# RGB_LED.net
KiCad netlist of a schematic drawn in Altium Designer
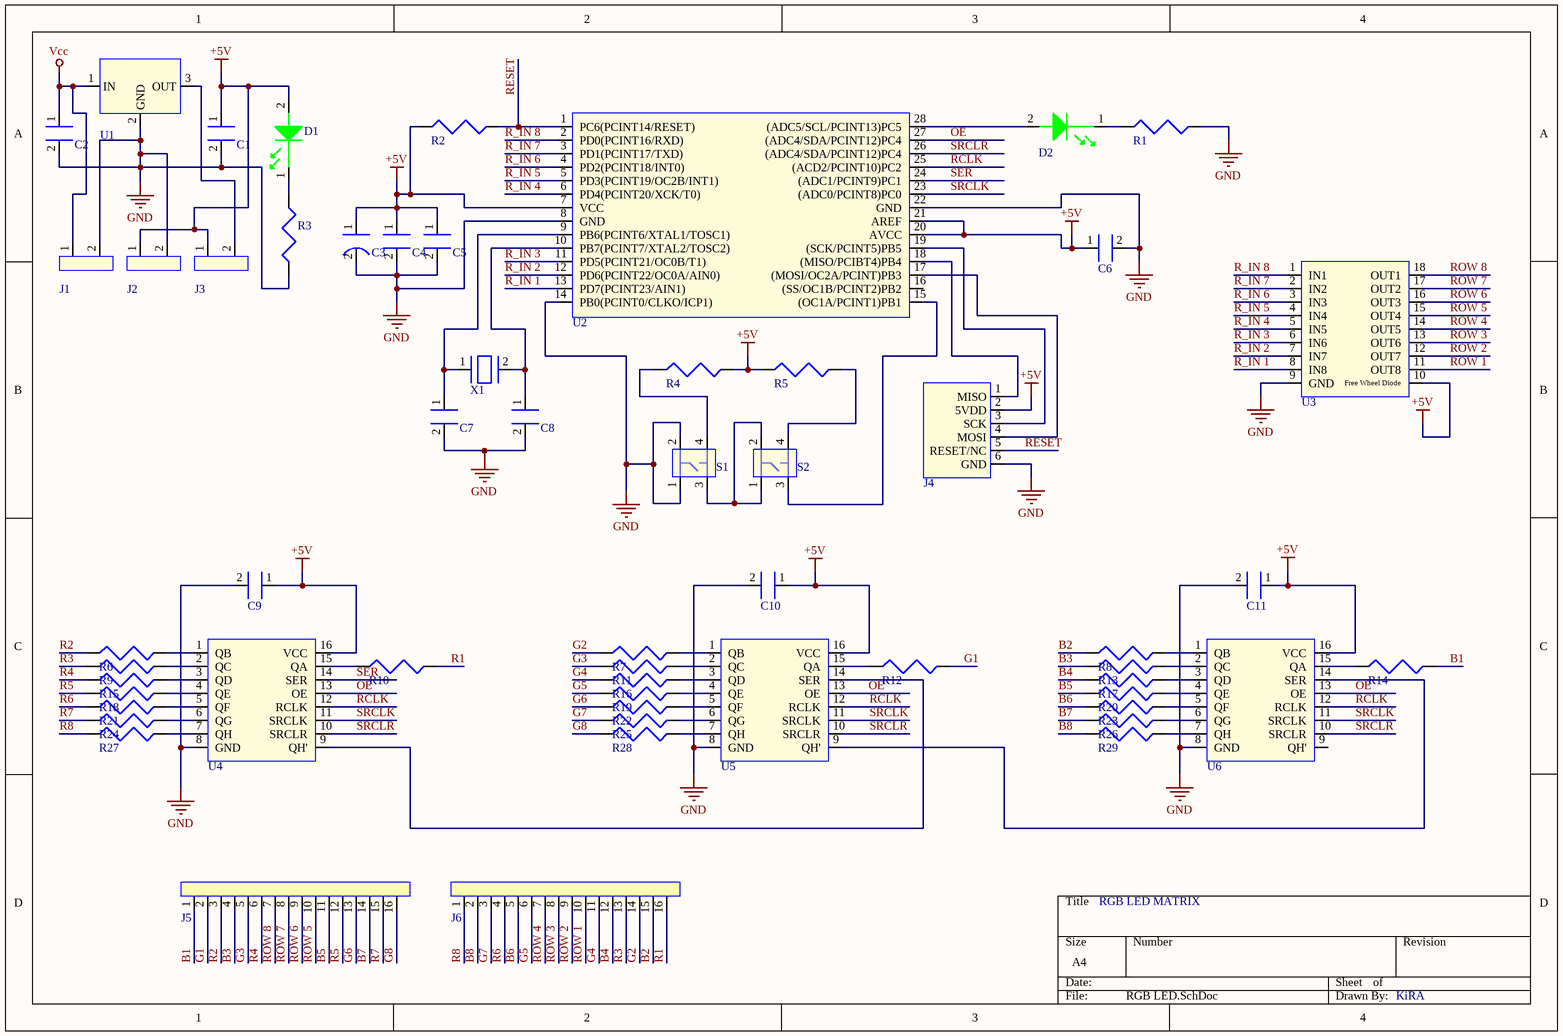
[diagram p0: RGB LED.SchDoc]

(export (version "E")
  (design (tool "Eeschema 10.0.6"))
  (components
    (comp (ref "C1")
      (value "10uF")
      (footprint "Cap 10uF 0805")
      (libsource (lib "RGB LED") (part "10uF 0805"))
    )
    (comp (ref "C2")
      (value "10uF")
      (footprint "Cap 10uF 0805")
      (libsource (lib "RGB LED") (part "10uF 0805"))
    )
    (comp (ref "C3")
      (value "47uF")
      (footprint "cap 47uF radial can")
      (fields
        (field (name "MANUFACTURER") "Panasonic Electronic Components")
        (field (name "TOLERANCE") "±20%")
      )
      (libsource (lib "RGB LED") (part "47uF Radial, Can -SMD"))
    )
    (comp (ref "C4")
      (value "10uF")
      (footprint "Cap 10uF 0805")
      (libsource (lib "RGB LED") (part "10uF 0805"))
    )
    (comp (ref "C5")
      (value "0.1uF")
      (footprint "Cap 0.1uF 0805")
      (libsource (lib "RGB LED") (part "0.1uF 0805"))
    )
    (comp (ref "C6")
      (value "0.1uF")
      (footprint "Cap 0.1uF 0805")
      (libsource (lib "RGB LED") (part "0.1uF 0805"))
    )
    (comp (ref "C7")
      (value "22pF")
      (footprint "CAP 22pF 0805")
      (libsource (lib "RGB LED") (part "22pF 0805"))
    )
    (comp (ref "C8")
      (value "22pF")
      (footprint "CAP 22pF 0805")
      (libsource (lib "RGB LED") (part "22pF 0805"))
    )
    (comp (ref "C9")
      (value "0.1uF")
      (footprint "Cap 0.1uF 0805")
      (libsource (lib "RGB LED") (part "0.1uF 0805"))
    )
    (comp (ref "C10")
      (value "0.1uF")
      (footprint "Cap 0.1uF 0805")
      (libsource (lib "RGB LED") (part "0.1uF 0805"))
    )
    (comp (ref "C11")
      (value "0.1uF")
      (footprint "Cap 0.1uF 0805")
      (libsource (lib "RGB LED") (part "0.1uF 0805"))
    )
    (comp (ref "D1")
      (value "LED 0805 Green")
      (footprint "LED 0805 Green")
      (fields (field (name "MANUFACTURER") "Lite-On Inc") (field (name "PART NO") "LTST-C171GKT"))
      (libsource (lib "RGB LED") (part "LED 0805 Green"))
    )
    (comp (ref "D2")
      (value "LED 0805 Green")
      (footprint "LED 0805 Green")
      (fields (field (name "MANUFACTURER") "Lite-On Inc") (field (name "PART NO") "LTST-C171GKT"))
      (libsource (lib "RGB LED") (part "LED 0805 Green"))
    )
    (comp (ref "J1")
      (value "Generic Header, 1X2 Vertical")
      (footprint "22232021")
      (fields (field (name "MANUFACTURER") "Molex") (field (name "PART NO") "22232021"))
      (libsource (lib "RGB LED") (part "2 pin male header"))
    )
    (comp (ref "J2")
      (value "Generic Header, 1X2 Vertical")
      (footprint "22232021")
      (fields (field (name "MANUFACTURER") "Molex") (field (name "PART NO") "22232021"))
      (libsource (lib "RGB LED") (part "2 pin male header"))
    )
    (comp (ref "J3")
      (value "Generic Header, 1X2 Vertical")
      (footprint "22232021")
      (fields (field (name "MANUFACTURER") "Molex") (field (name "PART NO") "22232021"))
      (libsource (lib "RGB LED") (part "2 pin male header"))
    )
    (comp (ref "J4")
      (value "6-Pin ISP header")
      (footprint "2X3 ISP header")
      (libsource (lib "RGB LED") (part "6-Pin ISP header"))
    )
    (comp (ref "J5")
      (value "16pin felmale header")
      (footprint "16 pins female header")
      (fields (field (name "MANUFACTURER") "4ucon technology inc"))
      (libsource (lib "RGB LED") (part "16pin felmale header"))
    )
    (comp (ref "J6")
      (value "16pin felmale header")
      (footprint "16 pins female header")
      (fields (field (name "MANUFACTURER") "4ucon technology inc"))
      (libsource (lib "RGB LED") (part "16pin felmale header"))
    )
    (comp (ref "R1")
      (value "200R")
      (footprint "RES 200R 0805")
      (fields
        (field (name "MANUFACTURER") "KOA Speer Electronics Inc")
        (field (name "PART NO") "RK73B2A")
        (field (name "POWER") "1/4W")
      )
      (libsource (lib "RGB LED") (part "Resistor 0805 200R"))
    )
    (comp (ref "R2")
      (value "10K")
      (footprint "RES 10K 0805")
      (fields
        (field (name "MANUFACTURER") "KOA Speer Electronics Inc")
        (field (name "PART NO") "RK73B2A")
        (field (name "POWER") "1/4W")
      )
      (libsource (lib "RGB LED") (part "Resistor 0805 10K"))
    )
    (comp (ref "R3")
      (value "200R")
      (footprint "RES 200R 0805")
      (fields
        (field (name "MANUFACTURER") "KOA Speer Electronics Inc")
        (field (name "PART NO") "RK73B2A")
        (field (name "POWER") "1/4W")
      )
      (libsource (lib "RGB LED") (part "Resistor 0805 200R"))
    )
    (comp (ref "R4")
      (value "10K")
      (footprint "RES 10K 0805")
      (fields
        (field (name "MANUFACTURER") "KOA Speer Electronics Inc")
        (field (name "PART NO") "RK73B2A")
        (field (name "POWER") "1/4W")
      )
      (libsource (lib "RGB LED") (part "Resistor 0805 10K"))
    )
    (comp (ref "R5")
      (value "10K")
      (footprint "RES 10K 0805")
      (fields
        (field (name "MANUFACTURER") "KOA Speer Electronics Inc")
        (field (name "PART NO") "RK73B2A")
        (field (name "POWER") "1/4W")
      )
      (libsource (lib "RGB LED") (part "Resistor 0805 10K"))
    )
    (comp (ref "R6")
      (value "Resistor 0805 100R")
      (footprint "RES 100R 0805")
      (fields
        (field (name "MANUFACTURER") "KOA Speer Electronics Inc")
        (field (name "PART NO") "RK73B2A")
        (field (name "POWER") "1/4W")
      )
      (libsource (lib "RGB LED") (part "Resistor 0805 100R"))
    )
    (comp (ref "R7")
      (value "Resistor 0805 100R")
      (footprint "RES 100R 0805")
      (fields
        (field (name "MANUFACTURER") "KOA Speer Electronics Inc")
        (field (name "PART NO") "RK73B2A")
        (field (name "POWER") "1/4W")
      )
      (libsource (lib "RGB LED") (part "Resistor 0805 100R"))
    )
    (comp (ref "R8")
      (value "Resistor 0805 100R")
      (footprint "RES 100R 0805")
      (fields
        (field (name "MANUFACTURER") "KOA Speer Electronics Inc")
        (field (name "PART NO") "RK73B2A")
        (field (name "POWER") "1/4W")
      )
      (libsource (lib "RGB LED") (part "Resistor 0805 100R"))
    )
    (comp (ref "R9")
      (value "Resistor 0805 100R")
      (footprint "RES 100R 0805")
      (fields
        (field (name "MANUFACTURER") "KOA Speer Electronics Inc")
        (field (name "PART NO") "RK73B2A")
        (field (name "POWER") "1/4W")
      )
      (libsource (lib "RGB LED") (part "Resistor 0805 100R"))
    )
    (comp (ref "R10")
      (value "Resistor 0805 100R")
      (footprint "RES 100R 0805")
      (fields
        (field (name "MANUFACTURER") "KOA Speer Electronics Inc")
        (field (name "PART NO") "RK73B2A")
        (field (name "POWER") "1/4W")
      )
      (libsource (lib "RGB LED") (part "Resistor 0805 100R"))
    )
    (comp (ref "R11")
      (value "Resistor 0805 100R")
      (footprint "RES 100R 0805")
      (fields
        (field (name "MANUFACTURER") "KOA Speer Electronics Inc")
        (field (name "PART NO") "RK73B2A")
        (field (name "POWER") "1/4W")
      )
      (libsource (lib "RGB LED") (part "Resistor 0805 100R"))
    )
    (comp (ref "R12")
      (value "Resistor 0805 100R")
      (footprint "RES 100R 0805")
      (fields
        (field (name "MANUFACTURER") "KOA Speer Electronics Inc")
        (field (name "PART NO") "RK73B2A")
        (field (name "POWER") "1/4W")
      )
      (libsource (lib "RGB LED") (part "Resistor 0805 100R"))
    )
    (comp (ref "R13")
      (value "Resistor 0805 100R")
      (footprint "RES 100R 0805")
      (fields
        (field (name "MANUFACTURER") "KOA Speer Electronics Inc")
        (field (name "PART NO") "RK73B2A")
        (field (name "POWER") "1/4W")
      )
      (libsource (lib "RGB LED") (part "Resistor 0805 100R"))
    )
    (comp (ref "R14")
      (value "Resistor 0805 100R")
      (footprint "RES 100R 0805")
      (fields
        (field (name "MANUFACTURER") "KOA Speer Electronics Inc")
        (field (name "PART NO") "RK73B2A")
        (field (name "POWER") "1/4W")
      )
      (libsource (lib "RGB LED") (part "Resistor 0805 100R"))
    )
    (comp (ref "R15")
      (value "Resistor 0805 100R")
      (footprint "RES 100R 0805")
      (fields
        (field (name "MANUFACTURER") "KOA Speer Electronics Inc")
        (field (name "PART NO") "RK73B2A")
        (field (name "POWER") "1/4W")
      )
      (libsource (lib "RGB LED") (part "Resistor 0805 100R"))
    )
    (comp (ref "R16")
      (value "Resistor 0805 100R")
      (footprint "RES 100R 0805")
      (fields
        (field (name "MANUFACTURER") "KOA Speer Electronics Inc")
        (field (name "PART NO") "RK73B2A")
        (field (name "POWER") "1/4W")
      )
      (libsource (lib "RGB LED") (part "Resistor 0805 100R"))
    )
    (comp (ref "R17")
      (value "Resistor 0805 100R")
      (footprint "RES 100R 0805")
      (fields
        (field (name "MANUFACTURER") "KOA Speer Electronics Inc")
        (field (name "PART NO") "RK73B2A")
        (field (name "POWER") "1/4W")
      )
      (libsource (lib "RGB LED") (part "Resistor 0805 100R"))
    )
    (comp (ref "R18")
      (value "Resistor 0805 100R")
      (footprint "RES 100R 0805")
      (fields
        (field (name "MANUFACTURER") "KOA Speer Electronics Inc")
        (field (name "PART NO") "RK73B2A")
        (field (name "POWER") "1/4W")
      )
      (libsource (lib "RGB LED") (part "Resistor 0805 100R"))
    )
    (comp (ref "R19")
      (value "Resistor 0805 100R")
      (footprint "RES 100R 0805")
      (fields
        (field (name "MANUFACTURER") "KOA Speer Electronics Inc")
        (field (name "PART NO") "RK73B2A")
        (field (name "POWER") "1/4W")
      )
      (libsource (lib "RGB LED") (part "Resistor 0805 100R"))
    )
    (comp (ref "R20")
      (value "Resistor 0805 100R")
      (footprint "RES 100R 0805")
      (fields
        (field (name "MANUFACTURER") "KOA Speer Electronics Inc")
        (field (name "PART NO") "RK73B2A")
        (field (name "POWER") "1/4W")
      )
      (libsource (lib "RGB LED") (part "Resistor 0805 100R"))
    )
    (comp (ref "R21")
      (value "Resistor 0805 100R")
      (footprint "RES 100R 0805")
      (fields
        (field (name "MANUFACTURER") "KOA Speer Electronics Inc")
        (field (name "PART NO") "RK73B2A")
        (field (name "POWER") "1/4W")
      )
      (libsource (lib "RGB LED") (part "Resistor 0805 100R"))
    )
    (comp (ref "R22")
      (value "Resistor 0805 100R")
      (footprint "RES 100R 0805")
      (fields
        (field (name "MANUFACTURER") "KOA Speer Electronics Inc")
        (field (name "PART NO") "RK73B2A")
        (field (name "POWER") "1/4W")
      )
      (libsource (lib "RGB LED") (part "Resistor 0805 100R"))
    )
    (comp (ref "R23")
      (value "Resistor 0805 100R")
      (footprint "RES 100R 0805")
      (fields
        (field (name "MANUFACTURER") "KOA Speer Electronics Inc")
        (field (name "PART NO") "RK73B2A")
        (field (name "POWER") "1/4W")
      )
      (libsource (lib "RGB LED") (part "Resistor 0805 100R"))
    )
    (comp (ref "R24")
      (value "Resistor 0805 100R")
      (footprint "RES 100R 0805")
      (fields
        (field (name "MANUFACTURER") "KOA Speer Electronics Inc")
        (field (name "PART NO") "RK73B2A")
        (field (name "POWER") "1/4W")
      )
      (libsource (lib "RGB LED") (part "Resistor 0805 100R"))
    )
    (comp (ref "R25")
      (value "Resistor 0805 100R")
      (footprint "RES 100R 0805")
      (fields
        (field (name "MANUFACTURER") "KOA Speer Electronics Inc")
        (field (name "PART NO") "RK73B2A")
        (field (name "POWER") "1/4W")
      )
      (libsource (lib "RGB LED") (part "Resistor 0805 100R"))
    )
    (comp (ref "R26")
      (value "Resistor 0805 100R")
      (footprint "RES 100R 0805")
      (fields
        (field (name "MANUFACTURER") "KOA Speer Electronics Inc")
        (field (name "PART NO") "RK73B2A")
        (field (name "POWER") "1/4W")
      )
      (libsource (lib "RGB LED") (part "Resistor 0805 100R"))
    )
    (comp (ref "R27")
      (value "Resistor 0805 100R")
      (footprint "RES 100R 0805")
      (fields
        (field (name "MANUFACTURER") "KOA Speer Electronics Inc")
        (field (name "PART NO") "RK73B2A")
        (field (name "POWER") "1/4W")
      )
      (libsource (lib "RGB LED") (part "Resistor 0805 100R"))
    )
    (comp (ref "R28")
      (value "Resistor 0805 100R")
      (footprint "RES 100R 0805")
      (fields
        (field (name "MANUFACTURER") "KOA Speer Electronics Inc")
        (field (name "PART NO") "RK73B2A")
        (field (name "POWER") "1/4W")
      )
      (libsource (lib "RGB LED") (part "Resistor 0805 100R"))
    )
    (comp (ref "R29")
      (value "Resistor 0805 100R")
      (footprint "RES 100R 0805")
      (fields
        (field (name "MANUFACTURER") "KOA Speer Electronics Inc")
        (field (name "PART NO") "RK73B2A")
        (field (name "POWER") "1/4W")
      )
      (libsource (lib "RGB LED") (part "Resistor 0805 100R"))
    )
    (comp (ref "S1")
      (value "Tactile Switch")
      (footprint "Tactile Switch")
      (libsource (lib "RGB LED") (part "Tactile Switch"))
    )
    (comp (ref "S2")
      (value "Tactile Switch")
      (footprint "Tactile Switch")
      (libsource (lib "RGB LED") (part "Tactile Switch"))
    )
    (comp (ref "U1")
      (value "L7805CV")
      (footprint "L7805VC")
      (fields (field (name "MANUFACTURER") "STMicroelectronics"))
      (libsource (lib "RGB LED") (part "L7805CV"))
    )
    (comp (ref "U2")
      (value "ATmega328P")
      (footprint "ATmega328P")
      (fields (field (name "MANUFACTURER") "Microchip Technology"))
      (libsource (lib "RGB LED") (part "ATmega328P"))
    )
    (comp (ref "U3")
      (value "ULN2803A")
      (footprint "ULN2803A")
      (description "8-Darlington Arrays")
      (fields (field (name "MANUFACTURER") "STMicroelectronics"))
      (libsource (lib "RGB LED") (part "ULN2803A"))
    )
    (comp (ref "U4")
      (value "SN74HC595N")
      (footprint "SN74HC595N-SOP")
      (description "Shift Register")
      (fields (field (name "MANUFACTURER") "Texas Instrument"))
      (libsource (lib "RGB LED") (part "SN74HC595N"))
    )
    (comp (ref "U5")
      (value "SN74HC595N")
      (footprint "SN74HC595N-SOP")
      (description "Shift Register")
      (fields (field (name "MANUFACTURER") "Texas Instrument"))
      (libsource (lib "RGB LED") (part "SN74HC595N"))
    )
    (comp (ref "U6")
      (value "SN74HC595N")
      (footprint "SN74HC595N-SOP")
      (description "Shift Register")
      (fields (field (name "MANUFACTURER") "Texas Instrument"))
      (libsource (lib "RGB LED") (part "SN74HC595N"))
    )
    (comp (ref "X1")
      (value "Crystal 16MHz")
      (footprint "Crystal 16MHz")
      (fields (field (name "MANUFACTURER") "Abracon LLC") (field (name "PART NO") "ABL-16.000MHZ-B2"))
      (libsource (lib "RGB LED") (part "Crystal 16MHz"))
    )
  )
  (nets
    (net (code "1") (name "+5V") (class "Default")
      (node (ref "C1") (pin "1") (pinfunction "1_1") (pintype "passive"))
      (node (ref "C10") (pin "1") (pinfunction "1_1") (pintype "passive"))
      (node (ref "C11") (pin "1") (pinfunction "1_1") (pintype "passive"))
      (node (ref "C3") (pin "1") (pinfunction "1_1") (pintype "passive"))
      (node (ref "C4") (pin "1") (pinfunction "1_1") (pintype "passive"))
      (node (ref "C5") (pin "1") (pinfunction "1_1") (pintype "passive"))
      (node (ref "C6") (pin "1") (pinfunction "1_1") (pintype "passive"))
      (node (ref "C9") (pin "1") (pinfunction "1_1") (pintype "passive"))
      (node (ref "D1") (pin "2") (pinfunction "2_2") (pintype "passive"))
      (node (ref "J2") (pin "1") (pinfunction "+_1") (pintype "passive"))
      (node (ref "J3") (pin "1") (pinfunction "+_1") (pintype "passive"))
      (node (ref "J4") (pin "2") (pinfunction "5VDD_2") (pintype "passive"))
      (node (ref "R2") (pin "1") (pinfunction "1_1") (pintype "passive"))
      (node (ref "R4") (pin "2") (pinfunction "2_2") (pintype "passive"))
      (node (ref "R5") (pin "1") (pinfunction "1_1") (pintype "passive"))
      (node (ref "U2") (pin "20") (pinfunction "AVCC_20") (pintype "passive"))
      (node (ref "U2") (pin "21") (pinfunction "AREF_21") (pintype "passive"))
      (node (ref "U2") (pin "7") (pinfunction "VCC_7") (pintype "passive"))
      (node (ref "U3") (pin "10") (pinfunction "Free_Wheel_Diode_10") (pintype "passive"))
      (node (ref "U4") (pin "16") (pinfunction "VCC_16") (pintype "passive"))
      (node (ref "U5") (pin "16") (pinfunction "VCC_16") (pintype "passive"))
      (node (ref "U6") (pin "16") (pinfunction "VCC_16") (pintype "passive"))
    )
    (net (code "2") (name "/B1") (class "Default")
      (node (ref "J5") (pin "1") (pinfunction "1_1") (pintype "passive"))
      (node (ref "R14") (pin "2") (pinfunction "2_2") (pintype "passive"))
    )
    (net (code "3") (name "/B2") (class "Default")
      (node (ref "J6") (pin "15") (pinfunction "15_15") (pintype "passive"))
      (node (ref "R8") (pin "1") (pinfunction "1_1") (pintype "passive"))
    )
    (net (code "4") (name "/B3") (class "Default")
      (node (ref "J5") (pin "4") (pinfunction "4_4") (pintype "passive"))
      (node (ref "R13") (pin "1") (pinfunction "1_1") (pintype "passive"))
    )
    (net (code "5") (name "/B4") (class "Default")
      (node (ref "J6") (pin "12") (pinfunction "12_12") (pintype "passive"))
      (node (ref "R17") (pin "1") (pinfunction "1_1") (pintype "passive"))
    )
    (net (code "6") (name "/B5") (class "Default")
      (node (ref "J5") (pin "11") (pinfunction "11_11") (pintype "passive"))
      (node (ref "R20") (pin "1") (pinfunction "1_1") (pintype "passive"))
    )
    (net (code "7") (name "/B6") (class "Default")
      (node (ref "J6") (pin "5") (pinfunction "5_5") (pintype "passive"))
      (node (ref "R23") (pin "1") (pinfunction "1_1") (pintype "passive"))
    )
    (net (code "8") (name "/B7") (class "Default")
      (node (ref "J5") (pin "14") (pinfunction "14_14") (pintype "passive"))
      (node (ref "R26") (pin "1") (pinfunction "1_1") (pintype "passive"))
    )
    (net (code "9") (name "/B8") (class "Default")
      (node (ref "J6") (pin "2") (pinfunction "2_2") (pintype "passive"))
      (node (ref "R29") (pin "1") (pinfunction "1_1") (pintype "passive"))
    )
    (net (code "10") (name "/G1") (class "Default")
      (node (ref "J5") (pin "2") (pinfunction "2_2") (pintype "passive"))
      (node (ref "R12") (pin "2") (pinfunction "2_2") (pintype "passive"))
    )
    (net (code "11") (name "/G2") (class "Default")
      (node (ref "J6") (pin "14") (pinfunction "14_14") (pintype "passive"))
      (node (ref "R7") (pin "1") (pinfunction "1_1") (pintype "passive"))
    )
    (net (code "12") (name "/G3") (class "Default")
      (node (ref "J5") (pin "5") (pinfunction "5_5") (pintype "passive"))
      (node (ref "R11") (pin "1") (pinfunction "1_1") (pintype "passive"))
    )
    (net (code "13") (name "/G4") (class "Default")
      (node (ref "J6") (pin "11") (pinfunction "11_11") (pintype "passive"))
      (node (ref "R16") (pin "1") (pinfunction "1_1") (pintype "passive"))
    )
    (net (code "14") (name "/G5") (class "Default")
      (node (ref "J6") (pin "6") (pinfunction "6_6") (pintype "passive"))
      (node (ref "R19") (pin "1") (pinfunction "1_1") (pintype "passive"))
    )
    (net (code "15") (name "/G6") (class "Default")
      (node (ref "J5") (pin "13") (pinfunction "13_13") (pintype "passive"))
      (node (ref "R22") (pin "1") (pinfunction "1_1") (pintype "passive"))
    )
    (net (code "16") (name "/G7") (class "Default")
      (node (ref "J6") (pin "3") (pinfunction "3_3") (pintype "passive"))
      (node (ref "R25") (pin "1") (pinfunction "1_1") (pintype "passive"))
    )
    (net (code "17") (name "/G8") (class "Default")
      (node (ref "J5") (pin "16") (pinfunction "16_16") (pintype "passive"))
      (node (ref "R28") (pin "1") (pinfunction "1_1") (pintype "passive"))
    )
    (net (code "18") (name "/OE") (class "Default")
      (node (ref "U2") (pin "27") (pinfunction "(ADC4/SDA/PCINT12)PC4_27") (pintype "passive"))
      (node (ref "U4") (pin "13") (pinfunction "OE_13") (pintype "passive"))
      (node (ref "U5") (pin "13") (pinfunction "OE_13") (pintype "passive"))
      (node (ref "U6") (pin "13") (pinfunction "OE_13") (pintype "passive"))
    )
    (net (code "19") (name "/R1") (class "Default")
      (node (ref "J6") (pin "16") (pinfunction "16_16") (pintype "passive"))
      (node (ref "R10") (pin "2") (pinfunction "2_2") (pintype "passive"))
    )
    (net (code "20") (name "/R2") (class "Default")
      (node (ref "J5") (pin "3") (pinfunction "3_3") (pintype "passive"))
      (node (ref "R6") (pin "1") (pinfunction "1_1") (pintype "passive"))
    )
    (net (code "21") (name "/R3") (class "Default")
      (node (ref "J6") (pin "13") (pinfunction "13_13") (pintype "passive"))
      (node (ref "R9") (pin "1") (pinfunction "1_1") (pintype "passive"))
    )
    (net (code "22") (name "/R4") (class "Default")
      (node (ref "J5") (pin "6") (pinfunction "6_6") (pintype "passive"))
      (node (ref "R15") (pin "1") (pinfunction "1_1") (pintype "passive"))
    )
    (net (code "23") (name "/R5") (class "Default")
      (node (ref "J5") (pin "12") (pinfunction "12_12") (pintype "passive"))
      (node (ref "R18") (pin "1") (pinfunction "1_1") (pintype "passive"))
    )
    (net (code "24") (name "/R6") (class "Default")
      (node (ref "J6") (pin "4") (pinfunction "4_4") (pintype "passive"))
      (node (ref "R21") (pin "1") (pinfunction "1_1") (pintype "passive"))
    )
    (net (code "25") (name "/R7") (class "Default")
      (node (ref "J5") (pin "15") (pinfunction "15_15") (pintype "passive"))
      (node (ref "R24") (pin "1") (pinfunction "1_1") (pintype "passive"))
    )
    (net (code "26") (name "/R8") (class "Default")
      (node (ref "J6") (pin "1") (pinfunction "1_1") (pintype "passive"))
      (node (ref "R27") (pin "1") (pinfunction "1_1") (pintype "passive"))
    )
    (net (code "27") (name "/RCLK") (class "Default")
      (node (ref "U2") (pin "25") (pinfunction "(ACD2/PCINT10)PC2_25") (pintype "passive"))
      (node (ref "U4") (pin "12") (pinfunction "RCLK_12") (pintype "passive"))
      (node (ref "U5") (pin "12") (pinfunction "RCLK_12") (pintype "passive"))
      (node (ref "U6") (pin "12") (pinfunction "RCLK_12") (pintype "passive"))
    )
    (net (code "28") (name "/RESET") (class "Default")
      (node (ref "J4") (pin "5") (pinfunction "RESET/NC_5") (pintype "passive"))
      (node (ref "R2") (pin "2") (pinfunction "2_2") (pintype "passive"))
      (node (ref "U2") (pin "1") (pinfunction "PC6(PCINT14/RESET)_1") (pintype "passive"))
    )
    (net (code "29") (name "/ROW 1") (class "Default")
      (node (ref "J6") (pin "10") (pinfunction "10_10") (pintype "passive"))
      (node (ref "U3") (pin "11") (pinfunction "OUT8_11") (pintype "passive"))
    )
    (net (code "30") (name "/ROW 2") (class "Default")
      (node (ref "J6") (pin "9") (pinfunction "9_9") (pintype "passive"))
      (node (ref "U3") (pin "12") (pinfunction "OUT7_12") (pintype "passive"))
    )
    (net (code "31") (name "/ROW 3") (class "Default")
      (node (ref "J6") (pin "8") (pinfunction "8_8") (pintype "passive"))
      (node (ref "U3") (pin "13") (pinfunction "OUT6_13") (pintype "passive"))
    )
    (net (code "32") (name "/ROW 4") (class "Default")
      (node (ref "J6") (pin "7") (pinfunction "7_7") (pintype "passive"))
      (node (ref "U3") (pin "14") (pinfunction "OUT5_14") (pintype "passive"))
    )
    (net (code "33") (name "/ROW 5") (class "Default")
      (node (ref "J5") (pin "10") (pinfunction "10_10") (pintype "passive"))
      (node (ref "U3") (pin "15") (pinfunction "OUT4_15") (pintype "passive"))
    )
    (net (code "34") (name "/ROW 6") (class "Default")
      (node (ref "J5") (pin "9") (pinfunction "9_9") (pintype "passive"))
      (node (ref "U3") (pin "16") (pinfunction "OUT3_16") (pintype "passive"))
    )
    (net (code "35") (name "/ROW 7") (class "Default")
      (node (ref "J5") (pin "8") (pinfunction "8_8") (pintype "passive"))
      (node (ref "U3") (pin "17") (pinfunction "OUT2_17") (pintype "passive"))
    )
    (net (code "36") (name "/ROW 8") (class "Default")
      (node (ref "J5") (pin "7") (pinfunction "7_7") (pintype "passive"))
      (node (ref "U3") (pin "18") (pinfunction "OUT1_18") (pintype "passive"))
    )
    (net (code "37") (name "/R_IN 1") (class "Default")
      (node (ref "U2") (pin "13") (pinfunction "PD7(PCINT23/AIN1)_13") (pintype "passive"))
      (node (ref "U3") (pin "8") (pinfunction "IN8_8") (pintype "passive"))
    )
    (net (code "38") (name "/R_IN 2") (class "Default")
      (node (ref "U2") (pin "12") (pinfunction "PD6(PCINT22/OC0A/AIN0)_12") (pintype "passive"))
      (node (ref "U3") (pin "7") (pinfunction "IN7_7") (pintype "passive"))
    )
    (net (code "39") (name "/R_IN 3") (class "Default")
      (node (ref "U2") (pin "11") (pinfunction "PD5(PCINT21/OC0B/T1)_11") (pintype "passive"))
      (node (ref "U3") (pin "6") (pinfunction "IN6_6") (pintype "passive"))
    )
    (net (code "40") (name "/R_IN 4") (class "Default")
      (node (ref "U2") (pin "6") (pinfunction "PD4(PCINT20/XCK/T0)_6") (pintype "passive"))
      (node (ref "U3") (pin "5") (pinfunction "IN5_5") (pintype "passive"))
    )
    (net (code "41") (name "/R_IN 5") (class "Default")
      (node (ref "U2") (pin "5") (pinfunction "PD3(PCINT19/OC2B/INT1)_5") (pintype "passive"))
      (node (ref "U3") (pin "4") (pinfunction "IN4_4") (pintype "passive"))
    )
    (net (code "42") (name "/R_IN 6") (class "Default")
      (node (ref "U2") (pin "4") (pinfunction "PD2(PCINT18/INT0)_4") (pintype "passive"))
      (node (ref "U3") (pin "3") (pinfunction "IN3_3") (pintype "passive"))
    )
    (net (code "43") (name "/R_IN 7") (class "Default")
      (node (ref "U2") (pin "3") (pinfunction "PD1(PCINT17/TXD)_3") (pintype "passive"))
      (node (ref "U3") (pin "2") (pinfunction "IN2_2") (pintype "passive"))
    )
    (net (code "44") (name "/R_IN 8") (class "Default")
      (node (ref "U2") (pin "2") (pinfunction "PD0(PCINT16/RXD)_2") (pintype "passive"))
      (node (ref "U3") (pin "1") (pinfunction "IN1_1") (pintype "passive"))
    )
    (net (code "45") (name "/SER") (class "Default")
      (node (ref "U2") (pin "24") (pinfunction "(ADC1/PCINT9)PC1_24") (pintype "passive"))
      (node (ref "U4") (pin "14") (pinfunction "SER_14") (pintype "passive"))
    )
    (net (code "46") (name "/SRCLK") (class "Default")
      (node (ref "U2") (pin "23") (pinfunction "(ADC0/PCINT8)PC0_23") (pintype "passive"))
      (node (ref "U4") (pin "11") (pinfunction "SRCLK_11") (pintype "passive"))
      (node (ref "U5") (pin "11") (pinfunction "SRCLK_11") (pintype "passive"))
      (node (ref "U6") (pin "11") (pinfunction "SRCLK_11") (pintype "passive"))
    )
    (net (code "47") (name "/SRCLR") (class "Default")
      (node (ref "U2") (pin "26") (pinfunction "(ADC4/SDA/PCINT12)PC4_26") (pintype "passive"))
      (node (ref "U4") (pin "10") (pinfunction "SRCLR_10") (pintype "passive"))
      (node (ref "U5") (pin "10") (pinfunction "SRCLR_10") (pintype "passive"))
      (node (ref "U6") (pin "10") (pinfunction "SRCLR_10") (pintype "passive"))
    )
    (net (code "48") (name "GND") (class "Default")
      (node (ref "C1") (pin "2") (pinfunction "2_2") (pintype "passive"))
      (node (ref "C10") (pin "2") (pinfunction "2_2") (pintype "passive"))
      (node (ref "C11") (pin "2") (pinfunction "2_2") (pintype "passive"))
      (node (ref "C2") (pin "2") (pinfunction "2_2") (pintype "passive"))
      (node (ref "C3") (pin "2") (pinfunction "2_2") (pintype "passive"))
      (node (ref "C4") (pin "2") (pinfunction "2_2") (pintype "passive"))
      (node (ref "C5") (pin "2") (pinfunction "2_2") (pintype "passive"))
      (node (ref "C6") (pin "2") (pinfunction "2_2") (pintype "passive"))
      (node (ref "C7") (pin "2") (pinfunction "2_2") (pintype "passive"))
      (node (ref "C8") (pin "2") (pinfunction "2_2") (pintype "passive"))
      (node (ref "C9") (pin "2") (pinfunction "2_2") (pintype "passive"))
      (node (ref "J1") (pin "2") (pinfunction "-_2") (pintype "passive"))
      (node (ref "J2") (pin "2") (pinfunction "-_2") (pintype "passive"))
      (node (ref "J4") (pin "6") (pinfunction "GND_6") (pintype "passive"))
      (node (ref "R1") (pin "1") (pinfunction "1_1") (pintype "passive"))
      (node (ref "R3") (pin "1") (pinfunction "1_1") (pintype "passive"))
      (node (ref "S1") (pin "1") (pinfunction "1_1") (pintype "passive"))
      (node (ref "S1") (pin "2") (pinfunction "2_2") (pintype "passive"))
      (node (ref "U1") (pin "2") (pinfunction "GND_2") (pintype "passive"))
      (node (ref "U2") (pin "14") (pinfunction "PB0(PCINT0/CLKO/ICP1)_14") (pintype "passive"))
      (node (ref "U2") (pin "22") (pinfunction "GND_22") (pintype "passive"))
      (node (ref "U2") (pin "8") (pinfunction "GND_8") (pintype "passive"))
      (node (ref "U3") (pin "9") (pinfunction "GND_9") (pintype "passive"))
      (node (ref "U4") (pin "8") (pinfunction "GND_8") (pintype "passive"))
      (node (ref "U5") (pin "8") (pinfunction "GND_8") (pintype "passive"))
      (node (ref "U6") (pin "8") (pinfunction "GND_8") (pintype "passive"))
    )
    (net (code "49") (name "Net-(D1-Pad1)") (class "Default")
      (node (ref "D1") (pin "1") (pinfunction "1_1") (pintype "passive"))
      (node (ref "R3") (pin "2") (pinfunction "2_2") (pintype "passive"))
    )
    (net (code "50") (name "Net-(D2-Pad1)") (class "Default")
      (node (ref "D2") (pin "1") (pinfunction "1_1") (pintype "passive"))
      (node (ref "R1") (pin "2") (pinfunction "2_2") (pintype "passive"))
    )
    (net (code "51") (name "Net-(J3--)") (class "Default")
      (node (ref "J3") (pin "2") (pinfunction "-_2") (pintype "passive"))
      (node (ref "U1") (pin "3") (pinfunction "OUT_3") (pintype "passive"))
    )
    (net (code "52") (name "Net-(J4-MISO)") (class "Default")
      (node (ref "J4") (pin "1") (pinfunction "MISO_1") (pintype "passive"))
      (node (ref "U2") (pin "18") (pinfunction "(MISO/PCIBT4)PB4_18") (pintype "passive"))
    )
    (net (code "53") (name "Net-(J4-MOSI)") (class "Default")
      (node (ref "J4") (pin "4") (pinfunction "MOSI_4") (pintype "passive"))
      (node (ref "U2") (pin "17") (pinfunction "(MOSI/OC2A/PCINT)PB3_17") (pintype "passive"))
    )
    (net (code "54") (name "Net-(J4-SCK)") (class "Default")
      (node (ref "J4") (pin "3") (pinfunction "SCK_3") (pintype "passive"))
      (node (ref "U2") (pin "19") (pinfunction "(SCK/PCINT5)PB5_19") (pintype "passive"))
    )
    (net (code "55") (name "Net-(R4-Pad1)") (class "Default")
      (node (ref "R4") (pin "1") (pinfunction "1_1") (pintype "passive"))
      (node (ref "S1") (pin "4") (pinfunction "4_4") (pintype "passive"))
    )
    (net (code "56") (name "Net-(R5-Pad2)") (class "Default")
      (node (ref "R5") (pin "2") (pinfunction "2_2") (pintype "passive"))
      (node (ref "S2") (pin "4") (pinfunction "4_4") (pintype "passive"))
    )
    (net (code "57") (name "Net-(S1-Pad3)") (class "Default")
      (node (ref "S1") (pin "3") (pinfunction "3_3") (pintype "passive"))
      (node (ref "S2") (pin "1") (pinfunction "1_1") (pintype "passive"))
      (node (ref "S2") (pin "2") (pinfunction "2_2") (pintype "passive"))
    )
    (net (code "58") (name "Net-(U2-(ADC5{slash}SCL{slash}PCINT13)PC5)") (class "Default")
      (node (ref "D2") (pin "2") (pinfunction "2_2") (pintype "passive"))
      (node (ref "U2") (pin "28") (pinfunction "(ADC5/SCL/PCINT13)PC5_28") (pintype "passive"))
    )
    (net (code "59") (name "Net-(U2-(OC1A{slash}PCINT1)PB1)") (class "Default")
      (node (ref "S2") (pin "3") (pinfunction "3_3") (pintype "passive"))
      (node (ref "U2") (pin "15") (pinfunction "(OC1A/PCINT1)PB1_15") (pintype "passive"))
    )
    (net (code "60") (name "Net-(U2-PB6(PCINT6{slash}XTAL1{slash}TOSC1))") (class "Default")
      (node (ref "C7") (pin "1") (pinfunction "1_1") (pintype "passive"))
      (node (ref "U2") (pin "9") (pinfunction "PB6(PCINT6/XTAL1/TOSC1)_9") (pintype "passive"))
      (node (ref "X1") (pin "1") (pinfunction "1_1") (pintype "passive"))
    )
    (net (code "61") (name "Net-(U2-PB7(PCINT7{slash}XTAL2{slash}TOSC2))") (class "Default")
      (node (ref "C8") (pin "1") (pinfunction "1_1") (pintype "passive"))
      (node (ref "U2") (pin "10") (pinfunction "PB7(PCINT7/XTAL2/TOSC2)_10") (pintype "passive"))
      (node (ref "X1") (pin "2") (pinfunction "2_2") (pintype "passive"))
    )
    (net (code "62") (name "Net-(U4-QA)") (class "Default")
      (node (ref "R10") (pin "1") (pinfunction "1_1") (pintype "passive"))
      (node (ref "U4") (pin "15") (pinfunction "QA_15") (pintype "passive"))
    )
    (net (code "63") (name "Net-(U4-QB)") (class "Default")
      (node (ref "R6") (pin "2") (pinfunction "2_2") (pintype "passive"))
      (node (ref "U4") (pin "1") (pinfunction "QB_1") (pintype "passive"))
    )
    (net (code "64") (name "Net-(U4-QC)") (class "Default")
      (node (ref "R9") (pin "2") (pinfunction "2_2") (pintype "passive"))
      (node (ref "U4") (pin "2") (pinfunction "QC_2") (pintype "passive"))
    )
    (net (code "65") (name "Net-(U4-QD)") (class "Default")
      (node (ref "R15") (pin "2") (pinfunction "2_2") (pintype "passive"))
      (node (ref "U4") (pin "3") (pinfunction "QD_3") (pintype "passive"))
    )
    (net (code "66") (name "Net-(U4-QE)") (class "Default")
      (node (ref "R18") (pin "2") (pinfunction "2_2") (pintype "passive"))
      (node (ref "U4") (pin "4") (pinfunction "QE_4") (pintype "passive"))
    )
    (net (code "67") (name "Net-(U4-QF)") (class "Default")
      (node (ref "R21") (pin "2") (pinfunction "2_2") (pintype "passive"))
      (node (ref "U4") (pin "5") (pinfunction "QF_5") (pintype "passive"))
    )
    (net (code "68") (name "Net-(U4-QG)") (class "Default")
      (node (ref "R24") (pin "2") (pinfunction "2_2") (pintype "passive"))
      (node (ref "U4") (pin "6") (pinfunction "QG_6") (pintype "passive"))
    )
    (net (code "69") (name "Net-(U4-QH')") (class "Default")
      (node (ref "U4") (pin "9") (pinfunction "QH'_9") (pintype "passive"))
      (node (ref "U5") (pin "14") (pinfunction "SER_14") (pintype "passive"))
    )
    (net (code "70") (name "Net-(U4-QH)") (class "Default")
      (node (ref "R27") (pin "2") (pinfunction "2_2") (pintype "passive"))
      (node (ref "U4") (pin "7") (pinfunction "QH_7") (pintype "passive"))
    )
    (net (code "71") (name "Net-(U5-QA)") (class "Default")
      (node (ref "R12") (pin "1") (pinfunction "1_1") (pintype "passive"))
      (node (ref "U5") (pin "15") (pinfunction "QA_15") (pintype "passive"))
    )
    (net (code "72") (name "Net-(U5-QB)") (class "Default")
      (node (ref "R7") (pin "2") (pinfunction "2_2") (pintype "passive"))
      (node (ref "U5") (pin "1") (pinfunction "QB_1") (pintype "passive"))
    )
    (net (code "73") (name "Net-(U5-QC)") (class "Default")
      (node (ref "R11") (pin "2") (pinfunction "2_2") (pintype "passive"))
      (node (ref "U5") (pin "2") (pinfunction "QC_2") (pintype "passive"))
    )
    (net (code "74") (name "Net-(U5-QD)") (class "Default")
      (node (ref "R16") (pin "2") (pinfunction "2_2") (pintype "passive"))
      (node (ref "U5") (pin "3") (pinfunction "QD_3") (pintype "passive"))
    )
    (net (code "75") (name "Net-(U5-QE)") (class "Default")
      (node (ref "R19") (pin "2") (pinfunction "2_2") (pintype "passive"))
      (node (ref "U5") (pin "4") (pinfunction "QE_4") (pintype "passive"))
    )
    (net (code "76") (name "Net-(U5-QF)") (class "Default")
      (node (ref "R22") (pin "2") (pinfunction "2_2") (pintype "passive"))
      (node (ref "U5") (pin "5") (pinfunction "QF_5") (pintype "passive"))
    )
    (net (code "77") (name "Net-(U5-QG)") (class "Default")
      (node (ref "R25") (pin "2") (pinfunction "2_2") (pintype "passive"))
      (node (ref "U5") (pin "6") (pinfunction "QG_6") (pintype "passive"))
    )
    (net (code "78") (name "Net-(U5-QH')") (class "Default")
      (node (ref "U5") (pin "9") (pinfunction "QH'_9") (pintype "passive"))
      (node (ref "U6") (pin "14") (pinfunction "SER_14") (pintype "passive"))
    )
    (net (code "79") (name "Net-(U5-QH)") (class "Default")
      (node (ref "R28") (pin "2") (pinfunction "2_2") (pintype "passive"))
      (node (ref "U5") (pin "7") (pinfunction "QH_7") (pintype "passive"))
    )
    (net (code "80") (name "Net-(U6-QA)") (class "Default")
      (node (ref "R14") (pin "1") (pinfunction "1_1") (pintype "passive"))
      (node (ref "U6") (pin "15") (pinfunction "QA_15") (pintype "passive"))
    )
    (net (code "81") (name "Net-(U6-QB)") (class "Default")
      (node (ref "R8") (pin "2") (pinfunction "2_2") (pintype "passive"))
      (node (ref "U6") (pin "1") (pinfunction "QB_1") (pintype "passive"))
    )
    (net (code "82") (name "Net-(U6-QC)") (class "Default")
      (node (ref "R13") (pin "2") (pinfunction "2_2") (pintype "passive"))
      (node (ref "U6") (pin "2") (pinfunction "QC_2") (pintype "passive"))
    )
    (net (code "83") (name "Net-(U6-QD)") (class "Default")
      (node (ref "R17") (pin "2") (pinfunction "2_2") (pintype "passive"))
      (node (ref "U6") (pin "3") (pinfunction "QD_3") (pintype "passive"))
    )
    (net (code "84") (name "Net-(U6-QE)") (class "Default")
      (node (ref "R20") (pin "2") (pinfunction "2_2") (pintype "passive"))
      (node (ref "U6") (pin "4") (pinfunction "QE_4") (pintype "passive"))
    )
    (net (code "85") (name "Net-(U6-QF)") (class "Default")
      (node (ref "R23") (pin "2") (pinfunction "2_2") (pintype "passive"))
      (node (ref "U6") (pin "5") (pinfunction "QF_5") (pintype "passive"))
    )
    (net (code "86") (name "Net-(U6-QG)") (class "Default")
      (node (ref "R26") (pin "2") (pinfunction "2_2") (pintype "passive"))
      (node (ref "U6") (pin "6") (pinfunction "QG_6") (pintype "passive"))
    )
    (net (code "87") (name "Net-(U6-QH)") (class "Default")
      (node (ref "R29") (pin "2") (pinfunction "2_2") (pintype "passive"))
      (node (ref "U6") (pin "7") (pinfunction "QH_7") (pintype "passive"))
    )
    (net (code "88") (name "Vcc") (class "Default")
      (node (ref "C2") (pin "1") (pinfunction "1_1") (pintype "passive"))
      (node (ref "J1") (pin "1") (pinfunction "+_1") (pintype "passive"))
      (node (ref "U1") (pin "1") (pinfunction "IN_1") (pintype "passive"))
    )
    (net (code "89") (name "unconnected-(U2-(SS{slash}OC1B{slash}PCINT2)PB2-Pad16)") (class "Default")
      (node (ref "U2") (pin "16") (pinfunction "(SS/OC1B/PCINT2)PB2_16") (pintype "passive"))
    )
    (net (code "90") (name "unconnected-(U6-QH'-Pad9)") (class "Default")
      (node (ref "U6") (pin "9") (pinfunction "QH'_9") (pintype "passive"))
    )
  )
)
